# Passive_Filter_PCB_Design_Large_Board.net
KiCad netlist of a schematic drawn in EAGLE
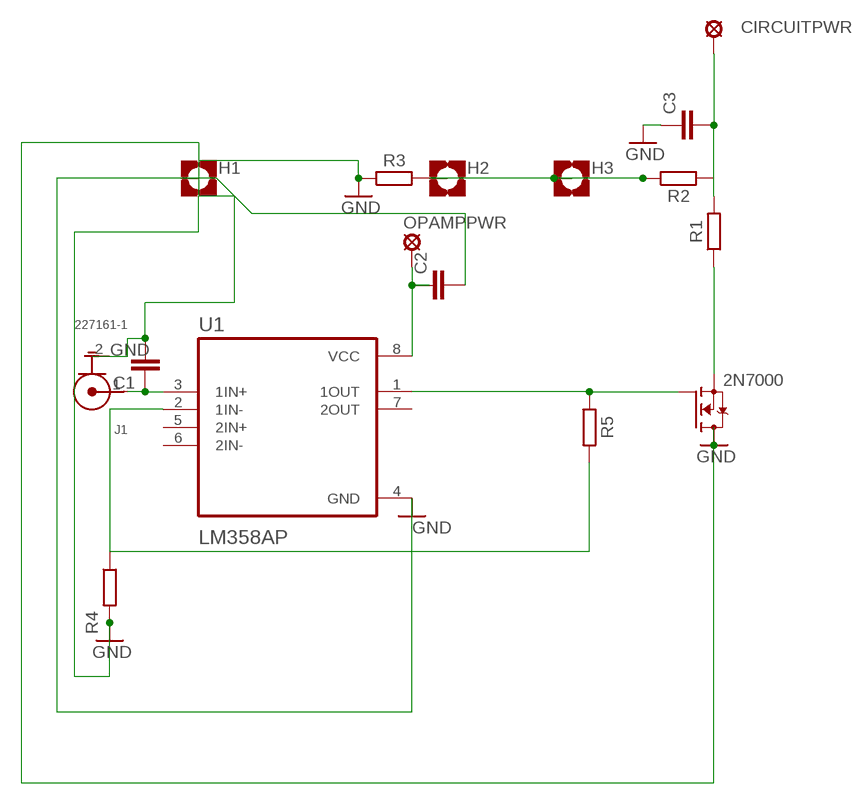
[diagram p0: schematic, sheet 1]

(export (version "E")
  (design (tool "Eeschema 10.0.6"))
  (components
    (comp (ref "C1")
      (value "C5/3.5")
      (footprint "eagle-import:C5B3.5")
      (libsource (lib "eagle-import") (part "C5/3.5"))
    )
    (comp (ref "C2")
      (value "C5/3.5")
      (footprint "eagle-import:C5B3.5")
      (libsource (lib "eagle-import") (part "C5/3.5"))
    )
    (comp (ref "C3")
      (value "C5/3.5")
      (footprint "eagle-import:C5B3.5")
      (libsource (lib "eagle-import") (part "C5/3.5"))
    )
    (comp (ref "CIRCUITPWR")
      (value "MCS10B")
      (footprint "eagle-import:MCS10B")
      (libsource (lib "eagle-import") (part "MCS10B"))
    )
    (comp (ref "H1")
      (value "MOUNT-PAD-SQUARE2.8")
      (footprint "eagle-import:2,8-PAD-SQUARE")
      (libsource (lib "eagle-import") (part "MOUNT-PAD-SQUARE2.8"))
    )
    (comp (ref "H2")
      (value "MOUNT-PAD-SQUARE2.8")
      (footprint "eagle-import:2,8-PAD-SQUARE")
      (libsource (lib "eagle-import") (part "MOUNT-PAD-SQUARE2.8"))
    )
    (comp (ref "H3")
      (value "MOUNT-PAD-SQUARE2.8")
      (footprint "eagle-import:2,8-PAD-SQUARE")
      (libsource (lib "eagle-import") (part "MOUNT-PAD-SQUARE2.8"))
    )
    (comp (ref "J1")
      (value "227161-1")
      (footprint "eagle-import:TE_227161-1")
      (fields (field (name "MF") "TE Connectivity"))
      (libsource (lib "eagle-import") (part "227161-1"))
    )
    (comp (ref "OPAMPPWR")
      (value "LSP10")
      (footprint "eagle-import:LSP10")
      (libsource (lib "eagle-import") (part "LSP10"))
    )
    (comp (ref "R1")
      (value "R_AXIAL-7.2MM-PITCH")
      (footprint "eagle-import:RESAD724W46L381D178B")
      (libsource (lib "eagle-import") (part "RAXIAL-7.2MM-PITCH_"))
    )
    (comp (ref "R2")
      (value "R_AXIAL-7.2MM-PITCH")
      (footprint "eagle-import:RESAD724W46L381D178B")
      (libsource (lib "eagle-import") (part "RAXIAL-7.2MM-PITCH_"))
    )
    (comp (ref "R3")
      (value "R_AXIAL-7.2MM-PITCH")
      (footprint "eagle-import:RESAD724W46L381D178B")
      (libsource (lib "eagle-import") (part "RAXIAL-7.2MM-PITCH_"))
    )
    (comp (ref "R4")
      (value "R_AXIAL-7.2MM-PITCH")
      (footprint "eagle-import:RESAD724W46L381D178B")
      (libsource (lib "eagle-import") (part "RAXIAL-7.2MM-PITCH_"))
    )
    (comp (ref "R5")
      (value "R_AXIAL-7.2MM-PITCH")
      (footprint "eagle-import:RESAD724W46L381D178B")
      (libsource (lib "eagle-import") (part "RAXIAL-7.2MM-PITCH_"))
    )
    (comp (ref "SHUNT")
      (value "2N7000")
      (footprint "eagle-import:TO92-")
      (fields (field (name "MF") "STMicroelectronics"))
      (libsource (lib "eagle-import") (part "2N7000"))
    )
    (comp (ref "U1")
      (value "LM358AP")
      (footprint "eagle-import:DIP794W45P254L959H508Q8")
      (fields (field (name "MF") "Texas Instruments"))
      (libsource (lib "eagle-import") (part "LM358AP"))
    )
  )
  (nets
    (net (code "1") (name "GND") (class "Default")
      (node (ref "C1") (pin "2") (pinfunction "2_2") (pintype "passive"))
      (node (ref "C2") (pin "2") (pinfunction "2_2") (pintype "passive"))
      (node (ref "C3") (pin "1") (pinfunction "1_1") (pintype "passive"))
      (node (ref "H1") (pin "B2,8") (pinfunction "MOUNT_B2,8") (pintype "passive"))
      (node (ref "J1") (pin "2") (pinfunction "G_2") (pintype "power_in"))
      (node (ref "R3") (pin "1") (pinfunction "1_1") (pintype "passive"))
      (node (ref "R4") (pin "2") (pinfunction "2_2") (pintype "passive"))
      (node (ref "SHUNT") (pin "1") (pinfunction "D_1") (pintype "passive"))
      (node (ref "U1") (pin "4") (pinfunction "GND_4") (pintype "power_in"))
    )
    (net (code "2") (name "Net-(C3-Pad2)") (class "Default")
      (node (ref "C3") (pin "2") (pinfunction "2_2") (pintype "passive"))
      (node (ref "CIRCUITPWR") (pin "MP") (pinfunction "MP_MP") (pintype "passive"))
      (node (ref "R1") (pin "2") (pinfunction "2_2") (pintype "passive"))
      (node (ref "R2") (pin "2") (pinfunction "2_2") (pintype "passive"))
    )
    (net (code "3") (name "Net-(H2-MOUNT)") (class "Default")
      (node (ref "H2") (pin "B2,8") (pinfunction "MOUNT_B2,8") (pintype "passive"))
      (node (ref "H3") (pin "B2,8") (pinfunction "MOUNT_B2,8") (pintype "passive"))
      (node (ref "R2") (pin "1") (pinfunction "1_1") (pintype "passive"))
      (node (ref "R3") (pin "2") (pinfunction "2_2") (pintype "passive"))
    )
    (net (code "4") (name "Net-(J1-C)") (class "Default")
      (node (ref "C1") (pin "1") (pinfunction "1_1") (pintype "passive"))
      (node (ref "J1") (pin "1") (pinfunction "C_1") (pintype "passive"))
      (node (ref "U1") (pin "3") (pinfunction "1IN+_3") (pintype "input"))
    )
    (net (code "5") (name "Net-(SHUNT-G)") (class "Default")
      (node (ref "R5") (pin "1") (pinfunction "1_1") (pintype "passive"))
      (node (ref "SHUNT") (pin "2") (pinfunction "G_2") (pintype "passive"))
      (node (ref "U1") (pin "1") (pinfunction "1OUT_1") (pintype "output"))
    )
    (net (code "6") (name "Net-(SHUNT-S)") (class "Default")
      (node (ref "R1") (pin "1") (pinfunction "1_1") (pintype "passive"))
      (node (ref "SHUNT") (pin "3") (pinfunction "S_3") (pintype "passive"))
    )
    (net (code "7") (name "Net-(U1-1IN-)") (class "Default")
      (node (ref "R4") (pin "1") (pinfunction "1_1") (pintype "passive"))
      (node (ref "R5") (pin "2") (pinfunction "2_2") (pintype "passive"))
      (node (ref "U1") (pin "2") (pinfunction "1IN-_2") (pintype "input"))
    )
    (net (code "8") (name "Net-(U1-VCC)") (class "Default")
      (node (ref "C2") (pin "1") (pinfunction "1_1") (pintype "passive"))
      (node (ref "OPAMPPWR") (pin "MP") (pinfunction "MP_MP") (pintype "passive"))
      (node (ref "U1") (pin "8") (pinfunction "VCC_8") (pintype "power_in"))
    )
    (net (code "9") (name "unconnected-(U1-2IN+-Pad5)") (class "Default")
      (node (ref "U1") (pin "5") (pinfunction "2IN+_5") (pintype "input"))
    )
    (net (code "10") (name "unconnected-(U1-2IN--Pad6)") (class "Default")
      (node (ref "U1") (pin "6") (pinfunction "2IN-_6") (pintype "input"))
    )
    (net (code "11") (name "unconnected-(U1-2OUT-Pad7)") (class "Default")
      (node (ref "U1") (pin "7") (pinfunction "2OUT_7") (pintype "output"))
    )
  )
)
